# stm32f407pin.net
KiCad netlist of a schematic drawn in Altium Designer
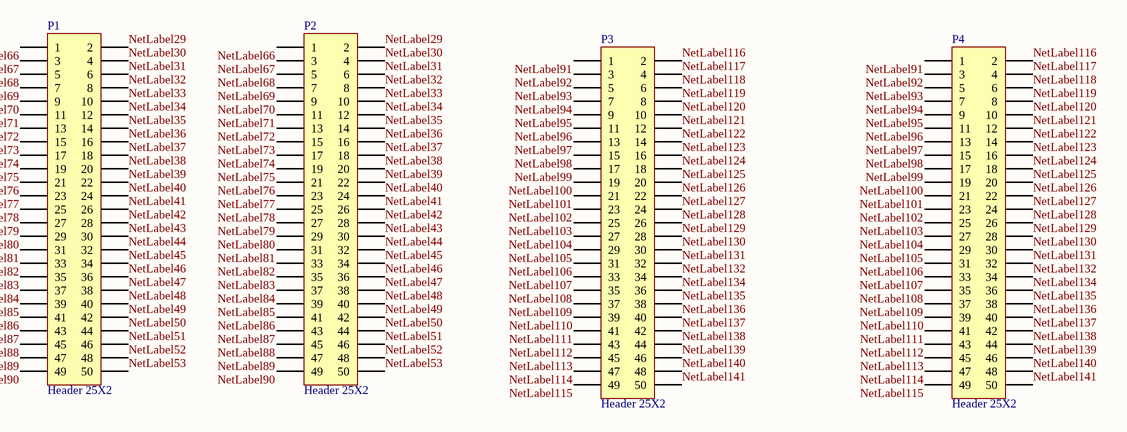
[diagram p0: stm32f407pin.SchDoc]

(export (version "E")
  (design (tool "Eeschema 10.0.6"))
  (components
    (comp (ref "P1")
      (value "Header 25X2")
      (footprint "HDR2X25")
      (description "Header, 25-Pin, Dual row")
      (fields (field (name "PUBLISHER") "Altium Limited"))
      (libsource (lib "Miscellaneous Connectors") (part "Header 25X2"))
    )
    (comp (ref "P2")
      (value "Header 25X2")
      (footprint "HDR2X25")
      (description "Header, 25-Pin, Dual row")
      (fields (field (name "PUBLISHER") "Altium Limited"))
      (libsource (lib "Miscellaneous Connectors") (part "Header 25X2"))
    )
    (comp (ref "P3")
      (value "Header 25X2")
      (footprint "HDR2X25")
      (description "Header, 25-Pin, Dual row")
      (fields (field (name "PUBLISHER") "Altium Limited"))
      (libsource (lib "Miscellaneous Connectors") (part "Header 25X2"))
    )
    (comp (ref "P4")
      (value "Header 25X2")
      (footprint "HDR2X25")
      (description "Header, 25-Pin, Dual row")
      (fields (field (name "PUBLISHER") "Altium Limited"))
      (libsource (lib "Miscellaneous Connectors") (part "Header 25X2"))
    )
  )
  (nets
    (net (code "1") (name "/NetLabel29") (class "Default")
      (node (ref "P1") (pin "2") (pinfunction "2_2") (pintype "passive"))
      (node (ref "P2") (pin "2") (pinfunction "2_2") (pintype "passive"))
    )
    (net (code "2") (name "/NetLabel30") (class "Default")
      (node (ref "P1") (pin "4") (pinfunction "4_4") (pintype "passive"))
      (node (ref "P2") (pin "4") (pinfunction "4_4") (pintype "passive"))
    )
    (net (code "3") (name "/NetLabel31") (class "Default")
      (node (ref "P1") (pin "6") (pinfunction "6_6") (pintype "passive"))
      (node (ref "P2") (pin "6") (pinfunction "6_6") (pintype "passive"))
    )
    (net (code "4") (name "/NetLabel32") (class "Default")
      (node (ref "P1") (pin "8") (pinfunction "8_8") (pintype "passive"))
      (node (ref "P2") (pin "8") (pinfunction "8_8") (pintype "passive"))
    )
    (net (code "5") (name "/NetLabel33") (class "Default")
      (node (ref "P1") (pin "10") (pinfunction "10_10") (pintype "passive"))
      (node (ref "P2") (pin "10") (pinfunction "10_10") (pintype "passive"))
    )
    (net (code "6") (name "/NetLabel34") (class "Default")
      (node (ref "P1") (pin "12") (pinfunction "12_12") (pintype "passive"))
      (node (ref "P2") (pin "12") (pinfunction "12_12") (pintype "passive"))
    )
    (net (code "7") (name "/NetLabel35") (class "Default")
      (node (ref "P1") (pin "14") (pinfunction "14_14") (pintype "passive"))
      (node (ref "P2") (pin "14") (pinfunction "14_14") (pintype "passive"))
    )
    (net (code "8") (name "/NetLabel36") (class "Default")
      (node (ref "P1") (pin "16") (pinfunction "16_16") (pintype "passive"))
      (node (ref "P2") (pin "16") (pinfunction "16_16") (pintype "passive"))
    )
    (net (code "9") (name "/NetLabel37") (class "Default")
      (node (ref "P1") (pin "18") (pinfunction "18_18") (pintype "passive"))
      (node (ref "P2") (pin "18") (pinfunction "18_18") (pintype "passive"))
    )
    (net (code "10") (name "/NetLabel38") (class "Default")
      (node (ref "P1") (pin "20") (pinfunction "20_20") (pintype "passive"))
      (node (ref "P2") (pin "20") (pinfunction "20_20") (pintype "passive"))
    )
    (net (code "11") (name "/NetLabel39") (class "Default")
      (node (ref "P1") (pin "22") (pinfunction "22_22") (pintype "passive"))
      (node (ref "P2") (pin "22") (pinfunction "22_22") (pintype "passive"))
    )
    (net (code "12") (name "/NetLabel40") (class "Default")
      (node (ref "P1") (pin "24") (pinfunction "24_24") (pintype "passive"))
      (node (ref "P2") (pin "24") (pinfunction "24_24") (pintype "passive"))
    )
    (net (code "13") (name "/NetLabel41") (class "Default")
      (node (ref "P1") (pin "26") (pinfunction "26_26") (pintype "passive"))
      (node (ref "P2") (pin "26") (pinfunction "26_26") (pintype "passive"))
    )
    (net (code "14") (name "/NetLabel42") (class "Default")
      (node (ref "P1") (pin "28") (pinfunction "28_28") (pintype "passive"))
      (node (ref "P2") (pin "28") (pinfunction "28_28") (pintype "passive"))
    )
    (net (code "15") (name "/NetLabel43") (class "Default")
      (node (ref "P1") (pin "30") (pinfunction "30_30") (pintype "passive"))
      (node (ref "P2") (pin "30") (pinfunction "30_30") (pintype "passive"))
    )
    (net (code "16") (name "/NetLabel44") (class "Default")
      (node (ref "P1") (pin "32") (pinfunction "32_32") (pintype "passive"))
      (node (ref "P2") (pin "32") (pinfunction "32_32") (pintype "passive"))
    )
    (net (code "17") (name "/NetLabel45") (class "Default")
      (node (ref "P1") (pin "34") (pinfunction "34_34") (pintype "passive"))
      (node (ref "P2") (pin "34") (pinfunction "34_34") (pintype "passive"))
    )
    (net (code "18") (name "/NetLabel46") (class "Default")
      (node (ref "P1") (pin "36") (pinfunction "36_36") (pintype "passive"))
      (node (ref "P2") (pin "36") (pinfunction "36_36") (pintype "passive"))
    )
    (net (code "19") (name "/NetLabel47") (class "Default")
      (node (ref "P1") (pin "38") (pinfunction "38_38") (pintype "passive"))
      (node (ref "P2") (pin "38") (pinfunction "38_38") (pintype "passive"))
    )
    (net (code "20") (name "/NetLabel48") (class "Default")
      (node (ref "P1") (pin "40") (pinfunction "40_40") (pintype "passive"))
      (node (ref "P2") (pin "40") (pinfunction "40_40") (pintype "passive"))
    )
    (net (code "21") (name "/NetLabel49") (class "Default")
      (node (ref "P1") (pin "42") (pinfunction "42_42") (pintype "passive"))
      (node (ref "P2") (pin "42") (pinfunction "42_42") (pintype "passive"))
    )
    (net (code "22") (name "/NetLabel50") (class "Default")
      (node (ref "P1") (pin "44") (pinfunction "44_44") (pintype "passive"))
      (node (ref "P2") (pin "44") (pinfunction "44_44") (pintype "passive"))
    )
    (net (code "23") (name "/NetLabel51") (class "Default")
      (node (ref "P1") (pin "46") (pinfunction "46_46") (pintype "passive"))
      (node (ref "P2") (pin "46") (pinfunction "46_46") (pintype "passive"))
    )
    (net (code "24") (name "/NetLabel52") (class "Default")
      (node (ref "P1") (pin "48") (pinfunction "48_48") (pintype "passive"))
      (node (ref "P2") (pin "48") (pinfunction "48_48") (pintype "passive"))
    )
    (net (code "25") (name "/NetLabel53") (class "Default")
      (node (ref "P1") (pin "50") (pinfunction "50_50") (pintype "passive"))
      (node (ref "P2") (pin "50") (pinfunction "50_50") (pintype "passive"))
    )
    (net (code "26") (name "/NetLabel66") (class "Default")
      (node (ref "P1") (pin "1") (pinfunction "1_1") (pintype "passive"))
      (node (ref "P2") (pin "1") (pinfunction "1_1") (pintype "passive"))
    )
    (net (code "27") (name "/NetLabel67") (class "Default")
      (node (ref "P1") (pin "3") (pinfunction "3_3") (pintype "passive"))
      (node (ref "P2") (pin "3") (pinfunction "3_3") (pintype "passive"))
    )
    (net (code "28") (name "/NetLabel68") (class "Default")
      (node (ref "P1") (pin "5") (pinfunction "5_5") (pintype "passive"))
      (node (ref "P2") (pin "5") (pinfunction "5_5") (pintype "passive"))
    )
    (net (code "29") (name "/NetLabel69") (class "Default")
      (node (ref "P1") (pin "7") (pinfunction "7_7") (pintype "passive"))
      (node (ref "P2") (pin "7") (pinfunction "7_7") (pintype "passive"))
    )
    (net (code "30") (name "/NetLabel70") (class "Default")
      (node (ref "P1") (pin "9") (pinfunction "9_9") (pintype "passive"))
      (node (ref "P2") (pin "9") (pinfunction "9_9") (pintype "passive"))
    )
    (net (code "31") (name "/NetLabel71") (class "Default")
      (node (ref "P1") (pin "11") (pinfunction "11_11") (pintype "passive"))
      (node (ref "P2") (pin "11") (pinfunction "11_11") (pintype "passive"))
    )
    (net (code "32") (name "/NetLabel72") (class "Default")
      (node (ref "P1") (pin "13") (pinfunction "13_13") (pintype "passive"))
      (node (ref "P2") (pin "13") (pinfunction "13_13") (pintype "passive"))
    )
    (net (code "33") (name "/NetLabel73") (class "Default")
      (node (ref "P1") (pin "15") (pinfunction "15_15") (pintype "passive"))
      (node (ref "P2") (pin "15") (pinfunction "15_15") (pintype "passive"))
    )
    (net (code "34") (name "/NetLabel74") (class "Default")
      (node (ref "P1") (pin "17") (pinfunction "17_17") (pintype "passive"))
      (node (ref "P2") (pin "17") (pinfunction "17_17") (pintype "passive"))
    )
    (net (code "35") (name "/NetLabel75") (class "Default")
      (node (ref "P1") (pin "19") (pinfunction "19_19") (pintype "passive"))
      (node (ref "P2") (pin "19") (pinfunction "19_19") (pintype "passive"))
    )
    (net (code "36") (name "/NetLabel76") (class "Default")
      (node (ref "P1") (pin "21") (pinfunction "21_21") (pintype "passive"))
      (node (ref "P2") (pin "21") (pinfunction "21_21") (pintype "passive"))
    )
    (net (code "37") (name "/NetLabel77") (class "Default")
      (node (ref "P1") (pin "23") (pinfunction "23_23") (pintype "passive"))
      (node (ref "P2") (pin "23") (pinfunction "23_23") (pintype "passive"))
    )
    (net (code "38") (name "/NetLabel78") (class "Default")
      (node (ref "P1") (pin "25") (pinfunction "25_25") (pintype "passive"))
      (node (ref "P2") (pin "25") (pinfunction "25_25") (pintype "passive"))
    )
    (net (code "39") (name "/NetLabel79") (class "Default")
      (node (ref "P1") (pin "27") (pinfunction "27_27") (pintype "passive"))
      (node (ref "P2") (pin "27") (pinfunction "27_27") (pintype "passive"))
    )
    (net (code "40") (name "/NetLabel80") (class "Default")
      (node (ref "P1") (pin "29") (pinfunction "29_29") (pintype "passive"))
      (node (ref "P2") (pin "29") (pinfunction "29_29") (pintype "passive"))
    )
    (net (code "41") (name "/NetLabel81") (class "Default")
      (node (ref "P1") (pin "31") (pinfunction "31_31") (pintype "passive"))
      (node (ref "P2") (pin "31") (pinfunction "31_31") (pintype "passive"))
    )
    (net (code "42") (name "/NetLabel82") (class "Default")
      (node (ref "P1") (pin "33") (pinfunction "33_33") (pintype "passive"))
      (node (ref "P2") (pin "33") (pinfunction "33_33") (pintype "passive"))
    )
    (net (code "43") (name "/NetLabel83") (class "Default")
      (node (ref "P1") (pin "35") (pinfunction "35_35") (pintype "passive"))
      (node (ref "P2") (pin "35") (pinfunction "35_35") (pintype "passive"))
    )
    (net (code "44") (name "/NetLabel84") (class "Default")
      (node (ref "P1") (pin "37") (pinfunction "37_37") (pintype "passive"))
      (node (ref "P2") (pin "37") (pinfunction "37_37") (pintype "passive"))
    )
    (net (code "45") (name "/NetLabel85") (class "Default")
      (node (ref "P1") (pin "39") (pinfunction "39_39") (pintype "passive"))
      (node (ref "P2") (pin "39") (pinfunction "39_39") (pintype "passive"))
    )
    (net (code "46") (name "/NetLabel86") (class "Default")
      (node (ref "P1") (pin "41") (pinfunction "41_41") (pintype "passive"))
      (node (ref "P2") (pin "41") (pinfunction "41_41") (pintype "passive"))
    )
    (net (code "47") (name "/NetLabel87") (class "Default")
      (node (ref "P1") (pin "43") (pinfunction "43_43") (pintype "passive"))
      (node (ref "P2") (pin "43") (pinfunction "43_43") (pintype "passive"))
    )
    (net (code "48") (name "/NetLabel88") (class "Default")
      (node (ref "P1") (pin "45") (pinfunction "45_45") (pintype "passive"))
      (node (ref "P2") (pin "45") (pinfunction "45_45") (pintype "passive"))
    )
    (net (code "49") (name "/NetLabel89") (class "Default")
      (node (ref "P1") (pin "47") (pinfunction "47_47") (pintype "passive"))
      (node (ref "P2") (pin "47") (pinfunction "47_47") (pintype "passive"))
    )
    (net (code "50") (name "/NetLabel90") (class "Default")
      (node (ref "P1") (pin "49") (pinfunction "49_49") (pintype "passive"))
      (node (ref "P2") (pin "49") (pinfunction "49_49") (pintype "passive"))
    )
    (net (code "51") (name "/NetLabel91") (class "Default")
      (node (ref "P3") (pin "1") (pinfunction "1_1") (pintype "passive"))
      (node (ref "P4") (pin "1") (pinfunction "1_1") (pintype "passive"))
    )
    (net (code "52") (name "/NetLabel92") (class "Default")
      (node (ref "P3") (pin "3") (pinfunction "3_3") (pintype "passive"))
      (node (ref "P4") (pin "3") (pinfunction "3_3") (pintype "passive"))
    )
    (net (code "53") (name "/NetLabel93") (class "Default")
      (node (ref "P3") (pin "5") (pinfunction "5_5") (pintype "passive"))
      (node (ref "P4") (pin "5") (pinfunction "5_5") (pintype "passive"))
    )
    (net (code "54") (name "/NetLabel94") (class "Default")
      (node (ref "P3") (pin "7") (pinfunction "7_7") (pintype "passive"))
      (node (ref "P4") (pin "7") (pinfunction "7_7") (pintype "passive"))
    )
    (net (code "55") (name "/NetLabel95") (class "Default")
      (node (ref "P3") (pin "9") (pinfunction "9_9") (pintype "passive"))
      (node (ref "P4") (pin "9") (pinfunction "9_9") (pintype "passive"))
    )
    (net (code "56") (name "/NetLabel96") (class "Default")
      (node (ref "P3") (pin "11") (pinfunction "11_11") (pintype "passive"))
      (node (ref "P4") (pin "11") (pinfunction "11_11") (pintype "passive"))
    )
    (net (code "57") (name "/NetLabel97") (class "Default")
      (node (ref "P3") (pin "13") (pinfunction "13_13") (pintype "passive"))
      (node (ref "P4") (pin "13") (pinfunction "13_13") (pintype "passive"))
    )
    (net (code "58") (name "/NetLabel98") (class "Default")
      (node (ref "P3") (pin "15") (pinfunction "15_15") (pintype "passive"))
      (node (ref "P4") (pin "15") (pinfunction "15_15") (pintype "passive"))
    )
    (net (code "59") (name "/NetLabel99") (class "Default")
      (node (ref "P3") (pin "17") (pinfunction "17_17") (pintype "passive"))
      (node (ref "P4") (pin "17") (pinfunction "17_17") (pintype "passive"))
    )
    (net (code "60") (name "/NetLabel100") (class "Default")
      (node (ref "P3") (pin "19") (pinfunction "19_19") (pintype "passive"))
      (node (ref "P4") (pin "19") (pinfunction "19_19") (pintype "passive"))
    )
    (net (code "61") (name "/NetLabel101") (class "Default")
      (node (ref "P3") (pin "21") (pinfunction "21_21") (pintype "passive"))
      (node (ref "P4") (pin "21") (pinfunction "21_21") (pintype "passive"))
    )
    (net (code "62") (name "/NetLabel102") (class "Default")
      (node (ref "P3") (pin "23") (pinfunction "23_23") (pintype "passive"))
      (node (ref "P4") (pin "23") (pinfunction "23_23") (pintype "passive"))
    )
    (net (code "63") (name "/NetLabel103") (class "Default")
      (node (ref "P3") (pin "25") (pinfunction "25_25") (pintype "passive"))
      (node (ref "P4") (pin "25") (pinfunction "25_25") (pintype "passive"))
    )
    (net (code "64") (name "/NetLabel104") (class "Default")
      (node (ref "P3") (pin "27") (pinfunction "27_27") (pintype "passive"))
      (node (ref "P4") (pin "27") (pinfunction "27_27") (pintype "passive"))
    )
    (net (code "65") (name "/NetLabel105") (class "Default")
      (node (ref "P3") (pin "29") (pinfunction "29_29") (pintype "passive"))
      (node (ref "P4") (pin "29") (pinfunction "29_29") (pintype "passive"))
    )
    (net (code "66") (name "/NetLabel106") (class "Default")
      (node (ref "P3") (pin "31") (pinfunction "31_31") (pintype "passive"))
      (node (ref "P4") (pin "31") (pinfunction "31_31") (pintype "passive"))
    )
    (net (code "67") (name "/NetLabel107") (class "Default")
      (node (ref "P3") (pin "33") (pinfunction "33_33") (pintype "passive"))
      (node (ref "P4") (pin "33") (pinfunction "33_33") (pintype "passive"))
    )
    (net (code "68") (name "/NetLabel108") (class "Default")
      (node (ref "P3") (pin "35") (pinfunction "35_35") (pintype "passive"))
      (node (ref "P4") (pin "35") (pinfunction "35_35") (pintype "passive"))
    )
    (net (code "69") (name "/NetLabel109") (class "Default")
      (node (ref "P3") (pin "37") (pinfunction "37_37") (pintype "passive"))
      (node (ref "P4") (pin "37") (pinfunction "37_37") (pintype "passive"))
    )
    (net (code "70") (name "/NetLabel110") (class "Default")
      (node (ref "P3") (pin "39") (pinfunction "39_39") (pintype "passive"))
      (node (ref "P4") (pin "39") (pinfunction "39_39") (pintype "passive"))
    )
    (net (code "71") (name "/NetLabel111") (class "Default")
      (node (ref "P3") (pin "41") (pinfunction "41_41") (pintype "passive"))
      (node (ref "P4") (pin "41") (pinfunction "41_41") (pintype "passive"))
    )
    (net (code "72") (name "/NetLabel112") (class "Default")
      (node (ref "P3") (pin "43") (pinfunction "43_43") (pintype "passive"))
      (node (ref "P4") (pin "43") (pinfunction "43_43") (pintype "passive"))
    )
    (net (code "73") (name "/NetLabel113") (class "Default")
      (node (ref "P3") (pin "45") (pinfunction "45_45") (pintype "passive"))
      (node (ref "P4") (pin "45") (pinfunction "45_45") (pintype "passive"))
    )
    (net (code "74") (name "/NetLabel114") (class "Default")
      (node (ref "P3") (pin "47") (pinfunction "47_47") (pintype "passive"))
      (node (ref "P4") (pin "47") (pinfunction "47_47") (pintype "passive"))
    )
    (net (code "75") (name "/NetLabel115") (class "Default")
      (node (ref "P3") (pin "49") (pinfunction "49_49") (pintype "passive"))
      (node (ref "P4") (pin "49") (pinfunction "49_49") (pintype "passive"))
    )
    (net (code "76") (name "/NetLabel116") (class "Default")
      (node (ref "P3") (pin "2") (pinfunction "2_2") (pintype "passive"))
      (node (ref "P4") (pin "2") (pinfunction "2_2") (pintype "passive"))
    )
    (net (code "77") (name "/NetLabel117") (class "Default")
      (node (ref "P3") (pin "4") (pinfunction "4_4") (pintype "passive"))
      (node (ref "P4") (pin "4") (pinfunction "4_4") (pintype "passive"))
    )
    (net (code "78") (name "/NetLabel118") (class "Default")
      (node (ref "P3") (pin "6") (pinfunction "6_6") (pintype "passive"))
      (node (ref "P4") (pin "6") (pinfunction "6_6") (pintype "passive"))
    )
    (net (code "79") (name "/NetLabel119") (class "Default")
      (node (ref "P3") (pin "8") (pinfunction "8_8") (pintype "passive"))
      (node (ref "P4") (pin "8") (pinfunction "8_8") (pintype "passive"))
    )
    (net (code "80") (name "/NetLabel120") (class "Default")
      (node (ref "P3") (pin "10") (pinfunction "10_10") (pintype "passive"))
      (node (ref "P4") (pin "10") (pinfunction "10_10") (pintype "passive"))
    )
    (net (code "81") (name "/NetLabel121") (class "Default")
      (node (ref "P3") (pin "12") (pinfunction "12_12") (pintype "passive"))
      (node (ref "P4") (pin "12") (pinfunction "12_12") (pintype "passive"))
    )
    (net (code "82") (name "/NetLabel122") (class "Default")
      (node (ref "P3") (pin "14") (pinfunction "14_14") (pintype "passive"))
      (node (ref "P4") (pin "14") (pinfunction "14_14") (pintype "passive"))
    )
    (net (code "83") (name "/NetLabel123") (class "Default")
      (node (ref "P3") (pin "16") (pinfunction "16_16") (pintype "passive"))
      (node (ref "P4") (pin "16") (pinfunction "16_16") (pintype "passive"))
    )
    (net (code "84") (name "/NetLabel124") (class "Default")
      (node (ref "P3") (pin "18") (pinfunction "18_18") (pintype "passive"))
      (node (ref "P4") (pin "18") (pinfunction "18_18") (pintype "passive"))
    )
    (net (code "85") (name "/NetLabel125") (class "Default")
      (node (ref "P3") (pin "20") (pinfunction "20_20") (pintype "passive"))
      (node (ref "P4") (pin "20") (pinfunction "20_20") (pintype "passive"))
    )
    (net (code "86") (name "/NetLabel126") (class "Default")
      (node (ref "P3") (pin "22") (pinfunction "22_22") (pintype "passive"))
      (node (ref "P4") (pin "22") (pinfunction "22_22") (pintype "passive"))
    )
    (net (code "87") (name "/NetLabel127") (class "Default")
      (node (ref "P3") (pin "24") (pinfunction "24_24") (pintype "passive"))
      (node (ref "P4") (pin "24") (pinfunction "24_24") (pintype "passive"))
    )
    (net (code "88") (name "/NetLabel128") (class "Default")
      (node (ref "P3") (pin "26") (pinfunction "26_26") (pintype "passive"))
      (node (ref "P4") (pin "26") (pinfunction "26_26") (pintype "passive"))
    )
    (net (code "89") (name "/NetLabel129") (class "Default")
      (node (ref "P3") (pin "28") (pinfunction "28_28") (pintype "passive"))
      (node (ref "P4") (pin "28") (pinfunction "28_28") (pintype "passive"))
    )
    (net (code "90") (name "/NetLabel130") (class "Default")
      (node (ref "P3") (pin "30") (pinfunction "30_30") (pintype "passive"))
      (node (ref "P4") (pin "30") (pinfunction "30_30") (pintype "passive"))
    )
    (net (code "91") (name "/NetLabel131") (class "Default")
      (node (ref "P3") (pin "32") (pinfunction "32_32") (pintype "passive"))
      (node (ref "P4") (pin "32") (pinfunction "32_32") (pintype "passive"))
    )
    (net (code "92") (name "/NetLabel132") (class "Default")
      (node (ref "P3") (pin "34") (pinfunction "34_34") (pintype "passive"))
      (node (ref "P4") (pin "34") (pinfunction "34_34") (pintype "passive"))
    )
    (net (code "93") (name "/NetLabel134") (class "Default")
      (node (ref "P3") (pin "36") (pinfunction "36_36") (pintype "passive"))
      (node (ref "P4") (pin "36") (pinfunction "36_36") (pintype "passive"))
    )
    (net (code "94") (name "/NetLabel135") (class "Default")
      (node (ref "P3") (pin "38") (pinfunction "38_38") (pintype "passive"))
      (node (ref "P4") (pin "38") (pinfunction "38_38") (pintype "passive"))
    )
    (net (code "95") (name "/NetLabel136") (class "Default")
      (node (ref "P3") (pin "40") (pinfunction "40_40") (pintype "passive"))
      (node (ref "P4") (pin "40") (pinfunction "40_40") (pintype "passive"))
    )
    (net (code "96") (name "/NetLabel137") (class "Default")
      (node (ref "P3") (pin "42") (pinfunction "42_42") (pintype "passive"))
      (node (ref "P4") (pin "42") (pinfunction "42_42") (pintype "passive"))
    )
    (net (code "97") (name "/NetLabel138") (class "Default")
      (node (ref "P3") (pin "44") (pinfunction "44_44") (pintype "passive"))
      (node (ref "P4") (pin "44") (pinfunction "44_44") (pintype "passive"))
    )
    (net (code "98") (name "/NetLabel139") (class "Default")
      (node (ref "P3") (pin "46") (pinfunction "46_46") (pintype "passive"))
      (node (ref "P4") (pin "46") (pinfunction "46_46") (pintype "passive"))
    )
    (net (code "99") (name "/NetLabel140") (class "Default")
      (node (ref "P3") (pin "48") (pinfunction "48_48") (pintype "passive"))
      (node (ref "P4") (pin "48") (pinfunction "48_48") (pintype "passive"))
    )
    (net (code "100") (name "/NetLabel141") (class "Default")
      (node (ref "P3") (pin "50") (pinfunction "50_50") (pintype "passive"))
      (node (ref "P4") (pin "50") (pinfunction "50_50") (pintype "passive"))
    )
  )
)
